# V2.net
KiCad netlist of a schematic drawn in EAGLE
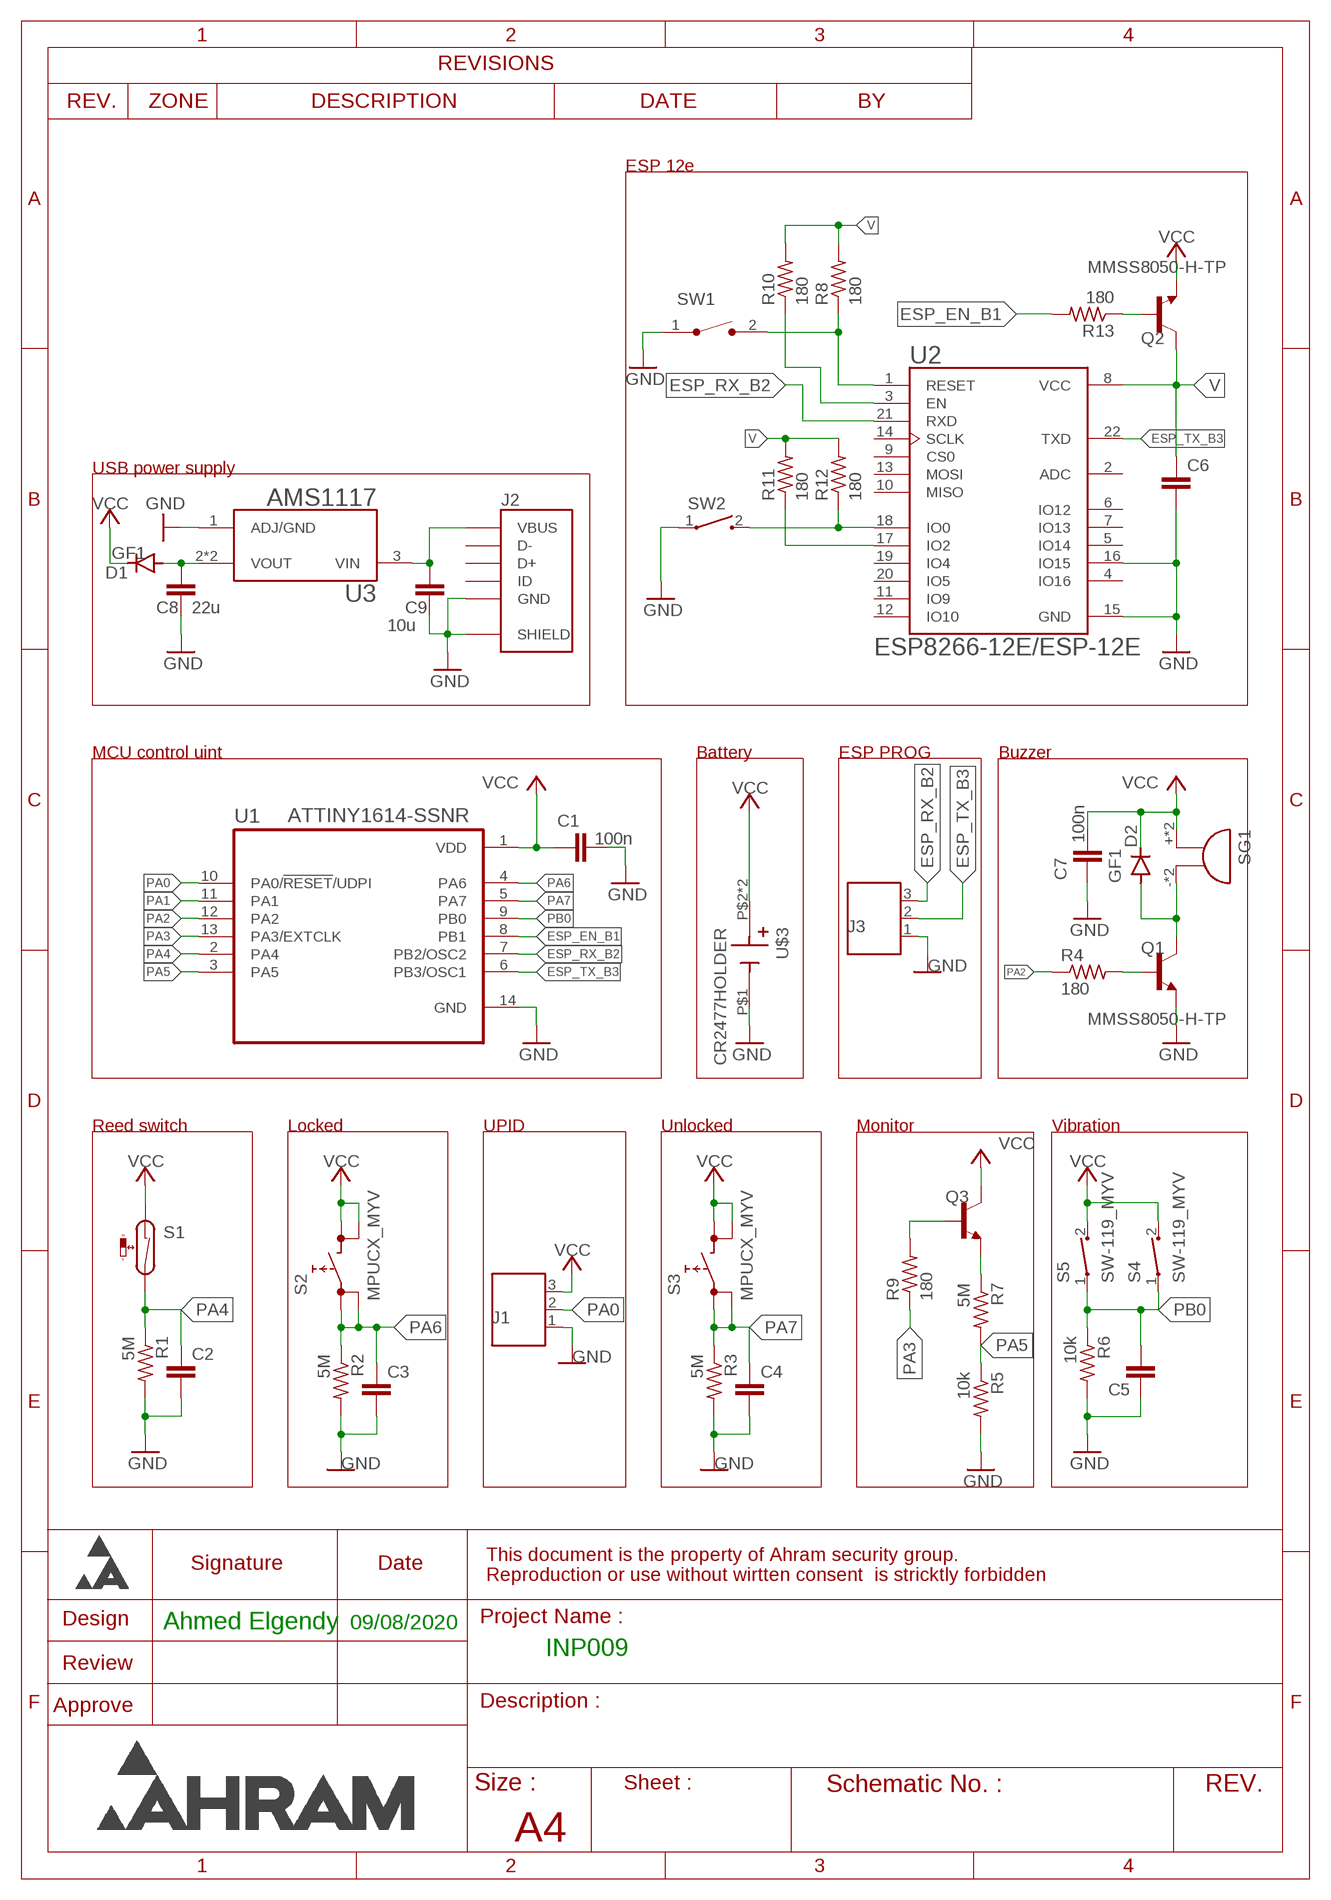
[diagram p0: schematic, sheet 1]

(export (version "E")
  (design (tool "Eeschema 10.0.6"))
  (components
    (comp (ref "C1")
      (value "100n")
      (footprint "eagle-import:C0805K")
      (libsource (lib "eagle-import") (part "C-EUC0805K"))
    )
    (comp (ref "C2")
      (value "C-EUC0805K")
      (footprint "eagle-import:C0805K")
      (libsource (lib "eagle-import") (part "C-EUC0805K"))
    )
    (comp (ref "C3")
      (value "C-EUC0805K")
      (footprint "eagle-import:C0805K")
      (libsource (lib "eagle-import") (part "C-EUC0805K"))
    )
    (comp (ref "C4")
      (value "C-EUC0805K")
      (footprint "eagle-import:C0805K")
      (libsource (lib "eagle-import") (part "C-EUC0805K"))
    )
    (comp (ref "C5")
      (value "C-EUC0805K")
      (footprint "eagle-import:C0805K")
      (libsource (lib "eagle-import") (part "C-EUC0805K"))
    )
    (comp (ref "C6")
      (value "C-EUC0805K")
      (footprint "eagle-import:C0805K")
      (libsource (lib "eagle-import") (part "C-EUC0805K"))
    )
    (comp (ref "C7")
      (value "100n")
      (footprint "eagle-import:C0805K")
      (libsource (lib "eagle-import") (part "C-EUC0805K"))
    )
    (comp (ref "C8")
      (value "22u")
      (footprint "eagle-import:C0805K")
      (libsource (lib "eagle-import") (part "C-EUC0805K"))
    )
    (comp (ref "C9")
      (value "10u")
      (footprint "eagle-import:C0805K")
      (libsource (lib "eagle-import") (part "C-EUC0805K"))
    )
    (comp (ref "D1")
      (value "GF1")
      (footprint "eagle-import:SMA-DO214AC")
      (libsource (lib "eagle-import") (part "GF1"))
    )
    (comp (ref "D2")
      (value "GF1")
      (footprint "eagle-import:SMA-DO214AC")
      (libsource (lib "eagle-import") (part "GF1"))
    )
    (comp (ref "J1")
      (value "691508110303")
      (footprint "eagle-import:691508110303")
      (libsource (lib "eagle-import") (part "691508110303"))
    )
    (comp (ref "J2")
      (value "USB3065-XX-00-A_REVE")
      (footprint "eagle-import:GCT_USB3065-XX-00-A_REVE")
      (fields (field (name "MF") "Global Connector Technology") (field (name "MP") "USB3065-30-00-A"))
      (libsource (lib "eagle-import") (part "USB3065-XX-00-A_REVE"))
    )
    (comp (ref "J3")
      (value "691508110303")
      (footprint "eagle-import:691508110303")
      (libsource (lib "eagle-import") (part "691508110303"))
    )
    (comp (ref "Q1")
      (value "MMSS8050-H-TP")
      (footprint "eagle-import:TRANS_MMSS8050-H-TP")
      (fields (field (name "MF") "Micro Commercial"))
      (libsource (lib "eagle-import") (part "MMSS8050-H-TP"))
    )
    (comp (ref "Q2")
      (value "MMSS8050-H-TP")
      (footprint "eagle-import:TRANS_MMSS8050-H-TP")
      (fields (field (name "MF") "Micro Commercial"))
      (libsource (lib "eagle-import") (part "MMSS8050-H-TP"))
    )
    (comp (ref "Q3")
      (value "MMSS8050-H-TP")
      (footprint "eagle-import:TRANS_MMSS8050-H-TP")
      (fields (field (name "MF") "Micro Commercial"))
      (libsource (lib "eagle-import") (part "MMSS8050-H-TP"))
    )
    (comp (ref "R1")
      (value "5M")
      (footprint "eagle-import:M0805")
      (libsource (lib "eagle-import") (part "R-US_M0805"))
    )
    (comp (ref "R2")
      (value "5M")
      (footprint "eagle-import:M0805")
      (libsource (lib "eagle-import") (part "R-US_M0805"))
    )
    (comp (ref "R3")
      (value "5M")
      (footprint "eagle-import:M0805")
      (libsource (lib "eagle-import") (part "R-US_M0805"))
    )
    (comp (ref "R4")
      (value "180")
      (footprint "eagle-import:M0805")
      (libsource (lib "eagle-import") (part "R-US_M0805"))
    )
    (comp (ref "R5")
      (value "10k")
      (footprint "eagle-import:M0805")
      (libsource (lib "eagle-import") (part "R-US_M0805"))
    )
    (comp (ref "R6")
      (value "10k")
      (footprint "eagle-import:M0805")
      (libsource (lib "eagle-import") (part "R-US_M0805"))
    )
    (comp (ref "R7")
      (value "5M")
      (footprint "eagle-import:M0805")
      (libsource (lib "eagle-import") (part "R-US_M0805"))
    )
    (comp (ref "R8")
      (value "180")
      (footprint "eagle-import:M0805")
      (libsource (lib "eagle-import") (part "R-US_M0805"))
    )
    (comp (ref "R9")
      (value "180")
      (footprint "eagle-import:M0805")
      (libsource (lib "eagle-import") (part "R-US_M0805"))
    )
    (comp (ref "R10")
      (value "180")
      (footprint "eagle-import:M0805")
      (libsource (lib "eagle-import") (part "R-US_M0805"))
    )
    (comp (ref "R11")
      (value "180")
      (footprint "eagle-import:M0805")
      (libsource (lib "eagle-import") (part "R-US_M0805"))
    )
    (comp (ref "R12")
      (value "180")
      (footprint "eagle-import:M0805")
      (libsource (lib "eagle-import") (part "R-US_M0805"))
    )
    (comp (ref "R13")
      (value "180")
      (footprint "eagle-import:M0805")
      (libsource (lib "eagle-import") (part "R-US_M0805"))
    )
    (comp (ref "S1")
      (value "RI80SMDM-MYV")
      (footprint "eagle-import:RI80SMDM-0510-J1")
      (libsource (lib "eagle-import") (part "RI80SMDM-MYV"))
    )
    (comp (ref "S2")
      (value "MPUCX_MYV")
      (footprint "eagle-import:MPUCX_MYV")
      (libsource (lib "eagle-import") (part "MPUCX_MYV"))
    )
    (comp (ref "S3")
      (value "MPUCX_MYV")
      (footprint "eagle-import:MPUCX_MYV")
      (libsource (lib "eagle-import") (part "MPUCX_MYV"))
    )
    (comp (ref "S4")
      (value "SW-119_MYV")
      (footprint "eagle-import:SW-119")
      (libsource (lib "eagle-import") (part "SW-119_MYV"))
    )
    (comp (ref "S5")
      (value "SW-119_MYV")
      (footprint "eagle-import:SW-119")
      (libsource (lib "eagle-import") (part "SW-119_MYV"))
    )
    (comp (ref "SG1")
      (value "CMI-9653S-SMT")
      (footprint "eagle-import:SMD_BUZZER")
      (libsource (lib "eagle-import") (part "CMI-9653S-SMT"))
    )
    (comp (ref "SW1")
      (value "FSMSM")
      (footprint "eagle-import:TE_FSMSM")
      (fields (field (name "COMMENT") "1437566-3") (field (name "MF") "TE Connectivity"))
      (libsource (lib "eagle-import") (part "FSMSM"))
    )
    (comp (ref "SW2")
      (value "1437566-3")
      (footprint "eagle-import:SW_1437566-3")
      (fields (field (name "MF") "TE Connectivity"))
      (libsource (lib "eagle-import") (part "1437566-3"))
    )
    (comp (ref "U$3")
      (value "CR2477HOLDER")
      (footprint "eagle-import:CR2477")
      (libsource (lib "eagle-import") (part "CR2477HOLDER"))
    )
    (comp (ref "U1")
      (value "ATTINY1614-SSNR")
      (footprint "eagle-import:SOIC127P600X175-14N")
      (fields (field (name "MF") "Microchip Technology"))
      (libsource (lib "eagle-import") (part "ATTINY1614-SSNR"))
    )
    (comp (ref "U2")
      (value "ESP8266-12E/ESP-12E")
      (footprint "eagle-import:XCVR_ESP8266-12E_ESP-12E")
      (fields (field (name "MF") "AI-Thinker"))
      (libsource (lib "eagle-import") (part "ESP8266-12E/ESP-12E"))
    )
    (comp (ref "U3")
      (value "AMS1117")
      (footprint "eagle-import:SOT229P700X180-4N")
      (fields (field (name "MF") "Seeed Technology"))
      (libsource (lib "eagle-import") (part "AMS1117"))
    )
  )
  (nets
    (net (code "1") (name "ESP_EN_B1") (class "Default")
      (node (ref "R13") (pin "2") (pinfunction "2_2") (pintype "passive"))
      (node (ref "U1") (pin "8") (pinfunction "PB1_8") (pintype "bidirectional"))
    )
    (net (code "2") (name "ESP_RX_B2") (class "Default")
      (node (ref "J3") (pin "3") (pinfunction "3_3") (pintype "passive"))
      (node (ref "U1") (pin "7") (pinfunction "PB2/OSC2_7") (pintype "bidirectional"))
      (node (ref "U2") (pin "21") (pinfunction "RXD_21") (pintype "input"))
    )
    (net (code "3") (name "ESP_TX_B3") (class "Default")
      (node (ref "J3") (pin "2") (pinfunction "2_2") (pintype "passive"))
      (node (ref "U1") (pin "6") (pinfunction "PB3/OSC1_6") (pintype "bidirectional"))
      (node (ref "U2") (pin "22") (pinfunction "TXD_22") (pintype "output"))
    )
    (net (code "4") (name "GND") (class "Default")
      (node (ref "C1") (pin "2") (pinfunction "2_2") (pintype "passive"))
      (node (ref "C2") (pin "2") (pinfunction "2_2") (pintype "passive"))
      (node (ref "C3") (pin "2") (pinfunction "2_2") (pintype "passive"))
      (node (ref "C4") (pin "2") (pinfunction "2_2") (pintype "passive"))
      (node (ref "C5") (pin "1") (pinfunction "1_1") (pintype "passive"))
      (node (ref "C6") (pin "2") (pinfunction "2_2") (pintype "passive"))
      (node (ref "C7") (pin "1") (pinfunction "1_1") (pintype "passive"))
      (node (ref "C8") (pin "1") (pinfunction "1_1") (pintype "passive"))
      (node (ref "C9") (pin "1") (pinfunction "1_1") (pintype "passive"))
      (node (ref "J1") (pin "1") (pinfunction "1_1") (pintype "passive"))
      (node (ref "J2") (pin "5") (pinfunction "GND_5") (pintype "power_in"))
      (node (ref "J2") (pin "6") (pinfunction "SHIELD_6") (pintype "power_in"))
      (node (ref "J2") (pin "7") (pinfunction "SHIELD_7") (pintype "power_in"))
      (node (ref "J2") (pin "8") (pinfunction "SHIELD_8") (pintype "power_in"))
      (node (ref "J2") (pin "9") (pinfunction "SHIELD_9") (pintype "power_in"))
      (node (ref "J3") (pin "1") (pinfunction "1_1") (pintype "passive"))
      (node (ref "Q1") (pin "2") (pinfunction "E_2") (pintype "passive"))
      (node (ref "R1") (pin "2") (pinfunction "2_2") (pintype "passive"))
      (node (ref "R2") (pin "2") (pinfunction "2_2") (pintype "passive"))
      (node (ref "R3") (pin "2") (pinfunction "2_2") (pintype "passive"))
      (node (ref "R5") (pin "2") (pinfunction "2_2") (pintype "passive"))
      (node (ref "R6") (pin "2") (pinfunction "2_2") (pintype "passive"))
      (node (ref "SW1") (pin "1") (pinfunction "1_1") (pintype "passive"))
      (node (ref "SW2") (pin "1") (pinfunction "1_1") (pintype "passive"))
      (node (ref "U$3") (pin "P$1") (pinfunction "-_P$1") (pintype "passive"))
      (node (ref "U1") (pin "14") (pinfunction "GND_14") (pintype "power_in"))
      (node (ref "U2") (pin "15") (pinfunction "GND_15") (pintype "power_in"))
      (node (ref "U2") (pin "16") (pinfunction "IO15_16") (pintype "bidirectional"))
      (node (ref "U3") (pin "1") (pinfunction "ADJ/GND_1") (pintype "power_in"))
    )
    (net (code "5") (name "Net-(C8-Pad2)") (class "Default")
      (node (ref "C8") (pin "2") (pinfunction "2_2") (pintype "passive"))
      (node (ref "D1") (pin "A") (pinfunction "A_A") (pintype "passive"))
      (node (ref "U3") (pin "2") (pinfunction "VOUT_2") (pintype "output"))
      (node (ref "U3") (pin "4") (pinfunction "VOUT_4") (pintype "output"))
    )
    (net (code "6") (name "Net-(J2-VBUS)") (class "Default")
      (node (ref "C9") (pin "2") (pinfunction "2_2") (pintype "passive"))
      (node (ref "J2") (pin "1") (pinfunction "VBUS_1") (pintype "power_in"))
      (node (ref "U3") (pin "3") (pinfunction "VIN_3") (pintype "input"))
    )
    (net (code "7") (name "Net-(Q1-B)") (class "Default")
      (node (ref "Q1") (pin "1") (pinfunction "B_1") (pintype "passive"))
      (node (ref "R4") (pin "2") (pinfunction "2_2") (pintype "passive"))
    )
    (net (code "8") (name "Net-(Q1-C)") (class "Default")
      (node (ref "D2") (pin "A") (pinfunction "A_A") (pintype "passive"))
      (node (ref "Q1") (pin "3") (pinfunction "C_3") (pintype "passive"))
      (node (ref "SG1") (pin "-") (pinfunction "-_-") (pintype "passive"))
      (node (ref "SG1") (pin "--") (pinfunction "-_--") (pintype "passive"))
    )
    (net (code "9") (name "Net-(Q2-B)") (class "Default")
      (node (ref "Q2") (pin "1") (pinfunction "B_1") (pintype "passive"))
      (node (ref "R13") (pin "1") (pinfunction "1_1") (pintype "passive"))
    )
    (net (code "10") (name "Net-(Q3-B)") (class "Default")
      (node (ref "Q3") (pin "1") (pinfunction "B_1") (pintype "passive"))
      (node (ref "R9") (pin "2") (pinfunction "2_2") (pintype "passive"))
    )
    (net (code "11") (name "Net-(Q3-E)") (class "Default")
      (node (ref "Q3") (pin "2") (pinfunction "E_2") (pintype "passive"))
      (node (ref "R7") (pin "1") (pinfunction "1_1") (pintype "passive"))
    )
    (net (code "12") (name "Net-(U2-EN)") (class "Default")
      (node (ref "R10") (pin "1") (pinfunction "1_1") (pintype "passive"))
      (node (ref "U2") (pin "3") (pinfunction "EN_3") (pintype "input"))
    )
    (net (code "13") (name "Net-(U2-IO0)") (class "Default")
      (node (ref "R12") (pin "1") (pinfunction "1_1") (pintype "passive"))
      (node (ref "SW2") (pin "2") (pinfunction "2_2") (pintype "passive"))
      (node (ref "U2") (pin "18") (pinfunction "IO0_18") (pintype "bidirectional"))
    )
    (net (code "14") (name "Net-(U2-IO2)") (class "Default")
      (node (ref "R11") (pin "1") (pinfunction "1_1") (pintype "passive"))
      (node (ref "U2") (pin "17") (pinfunction "IO2_17") (pintype "bidirectional"))
    )
    (net (code "15") (name "Net-(U2-RESET)") (class "Default")
      (node (ref "R8") (pin "1") (pinfunction "1_1") (pintype "passive"))
      (node (ref "SW1") (pin "2") (pinfunction "2_2") (pintype "passive"))
      (node (ref "U2") (pin "1") (pinfunction "RESET_1") (pintype "input"))
    )
    (net (code "16") (name "PA0") (class "Default")
      (node (ref "J1") (pin "2") (pinfunction "2_2") (pintype "passive"))
      (node (ref "U1") (pin "10") (pinfunction "PA0/~{RESET}/UDPI_10") (pintype "bidirectional"))
    )
    (net (code "17") (name "PA1") (class "Default")
      (node (ref "U1") (pin "11") (pinfunction "PA1_11") (pintype "bidirectional"))
    )
    (net (code "18") (name "PA2") (class "Default")
      (node (ref "R4") (pin "1") (pinfunction "1_1") (pintype "passive"))
      (node (ref "U1") (pin "12") (pinfunction "PA2_12") (pintype "bidirectional"))
    )
    (net (code "19") (name "PA3") (class "Default")
      (node (ref "R9") (pin "1") (pinfunction "1_1") (pintype "passive"))
      (node (ref "U1") (pin "13") (pinfunction "PA3/EXTCLK_13") (pintype "bidirectional"))
    )
    (net (code "20") (name "PA4") (class "Default")
      (node (ref "C2") (pin "1") (pinfunction "1_1") (pintype "passive"))
      (node (ref "R1") (pin "1") (pinfunction "1_1") (pintype "passive"))
      (node (ref "S1") (pin "P$2") (pinfunction "2_P$2") (pintype "passive"))
      (node (ref "U1") (pin "2") (pinfunction "PA4_2") (pintype "bidirectional"))
    )
    (net (code "21") (name "PA5") (class "Default")
      (node (ref "R5") (pin "1") (pinfunction "1_1") (pintype "passive"))
      (node (ref "R7") (pin "2") (pinfunction "2_2") (pintype "passive"))
      (node (ref "U1") (pin "3") (pinfunction "PA5_3") (pintype "bidirectional"))
    )
    (net (code "22") (name "PA6") (class "Default")
      (node (ref "C3") (pin "1") (pinfunction "1_1") (pintype "passive"))
      (node (ref "R2") (pin "1") (pinfunction "1_1") (pintype "passive"))
      (node (ref "S2") (pin "1") (pinfunction "1_1") (pintype "passive"))
      (node (ref "S2") (pin "2") (pinfunction "2_2") (pintype "passive"))
      (node (ref "U1") (pin "4") (pinfunction "PA6_4") (pintype "bidirectional"))
    )
    (net (code "23") (name "PA7") (class "Default")
      (node (ref "C4") (pin "1") (pinfunction "1_1") (pintype "passive"))
      (node (ref "R3") (pin "1") (pinfunction "1_1") (pintype "passive"))
      (node (ref "S3") (pin "1") (pinfunction "1_1") (pintype "passive"))
      (node (ref "S3") (pin "2") (pinfunction "2_2") (pintype "passive"))
      (node (ref "U1") (pin "5") (pinfunction "PA7_5") (pintype "bidirectional"))
    )
    (net (code "24") (name "PB0") (class "Default")
      (node (ref "C5") (pin "2") (pinfunction "2_2") (pintype "passive"))
      (node (ref "R6") (pin "1") (pinfunction "1_1") (pintype "passive"))
      (node (ref "S4") (pin "1") (pinfunction "1_1") (pintype "passive"))
      (node (ref "S5") (pin "1") (pinfunction "1_1") (pintype "passive"))
      (node (ref "U1") (pin "9") (pinfunction "PB0_9") (pintype "bidirectional"))
    )
    (net (code "25") (name "V") (class "Default")
      (node (ref "C6") (pin "1") (pinfunction "1_1") (pintype "passive"))
      (node (ref "Q2") (pin "3") (pinfunction "C_3") (pintype "passive"))
      (node (ref "R10") (pin "2") (pinfunction "2_2") (pintype "passive"))
      (node (ref "R11") (pin "2") (pinfunction "2_2") (pintype "passive"))
      (node (ref "R12") (pin "2") (pinfunction "2_2") (pintype "passive"))
      (node (ref "R8") (pin "2") (pinfunction "2_2") (pintype "passive"))
      (node (ref "U2") (pin "8") (pinfunction "VCC_8") (pintype "power_in"))
    )
    (net (code "26") (name "VCC") (class "Default")
      (node (ref "C1") (pin "1") (pinfunction "1_1") (pintype "passive"))
      (node (ref "C7") (pin "2") (pinfunction "2_2") (pintype "passive"))
      (node (ref "D1") (pin "K") (pinfunction "C_K") (pintype "passive"))
      (node (ref "D2") (pin "K") (pinfunction "C_K") (pintype "passive"))
      (node (ref "J1") (pin "3") (pinfunction "3_3") (pintype "passive"))
      (node (ref "Q2") (pin "2") (pinfunction "E_2") (pintype "passive"))
      (node (ref "Q3") (pin "3") (pinfunction "C_3") (pintype "passive"))
      (node (ref "S1") (pin "P$1") (pinfunction "1_P$1") (pintype "passive"))
      (node (ref "S2") (pin "3") (pinfunction "3_3") (pintype "passive"))
      (node (ref "S2") (pin "4") (pinfunction "4_4") (pintype "passive"))
      (node (ref "S3") (pin "3") (pinfunction "3_3") (pintype "passive"))
      (node (ref "S3") (pin "4") (pinfunction "4_4") (pintype "passive"))
      (node (ref "S4") (pin "2") (pinfunction "2_2") (pintype "passive"))
      (node (ref "S5") (pin "2") (pinfunction "2_2") (pintype "passive"))
      (node (ref "SG1") (pin "+") (pinfunction "+_+") (pintype "passive"))
      (node (ref "SG1") (pin "++") (pinfunction "+_++") (pintype "passive"))
      (node (ref "U$3") (pin "P$2") (pinfunction "+_P$2") (pintype "passive"))
      (node (ref "U$3") (pin "P$3") (pinfunction "+_P$3") (pintype "passive"))
      (node (ref "U1") (pin "1") (pinfunction "VDD_1") (pintype "power_in"))
    )
    (net (code "27") (name "unconnected-(J2-D+-Pad3)") (class "Default")
      (node (ref "J2") (pin "3") (pinfunction "D+_3") (pintype "bidirectional"))
    )
    (net (code "28") (name "unconnected-(J2-D--Pad2)") (class "Default")
      (node (ref "J2") (pin "2") (pinfunction "D-_2") (pintype "bidirectional"))
    )
    (net (code "29") (name "unconnected-(J2-ID-Pad4)") (class "Default")
      (node (ref "J2") (pin "4") (pinfunction "ID_4") (pintype "bidirectional"))
    )
    (net (code "30") (name "unconnected-(U2-ADC-Pad2)") (class "Default")
      (node (ref "U2") (pin "2") (pinfunction "ADC_2") (pintype "passive"))
    )
    (net (code "31") (name "unconnected-(U2-CS0-Pad9)") (class "Default")
      (node (ref "U2") (pin "9") (pinfunction "CS0_9") (pintype "input"))
    )
    (net (code "32") (name "unconnected-(U2-IO4-Pad19)") (class "Default")
      (node (ref "U2") (pin "19") (pinfunction "IO4_19") (pintype "bidirectional"))
    )
    (net (code "33") (name "unconnected-(U2-IO5-Pad20)") (class "Default")
      (node (ref "U2") (pin "20") (pinfunction "IO5_20") (pintype "bidirectional"))
    )
    (net (code "34") (name "unconnected-(U2-IO9-Pad11)") (class "Default")
      (node (ref "U2") (pin "11") (pinfunction "IO9_11") (pintype "bidirectional"))
    )
    (net (code "35") (name "unconnected-(U2-IO10-Pad12)") (class "Default")
      (node (ref "U2") (pin "12") (pinfunction "IO10_12") (pintype "bidirectional"))
    )
    (net (code "36") (name "unconnected-(U2-IO12-Pad6)") (class "Default")
      (node (ref "U2") (pin "6") (pinfunction "IO12_6") (pintype "bidirectional"))
    )
    (net (code "37") (name "unconnected-(U2-IO13-Pad7)") (class "Default")
      (node (ref "U2") (pin "7") (pinfunction "IO13_7") (pintype "bidirectional"))
    )
    (net (code "38") (name "unconnected-(U2-IO14-Pad5)") (class "Default")
      (node (ref "U2") (pin "5") (pinfunction "IO14_5") (pintype "bidirectional"))
    )
    (net (code "39") (name "unconnected-(U2-IO16-Pad4)") (class "Default")
      (node (ref "U2") (pin "4") (pinfunction "IO16_4") (pintype "bidirectional"))
    )
    (net (code "40") (name "unconnected-(U2-MISO-Pad10)") (class "Default")
      (node (ref "U2") (pin "10") (pinfunction "MISO_10") (pintype "bidirectional"))
    )
    (net (code "41") (name "unconnected-(U2-MOSI-Pad13)") (class "Default")
      (node (ref "U2") (pin "13") (pinfunction "MOSI_13") (pintype "bidirectional"))
    )
    (net (code "42") (name "unconnected-(U2-SCLK-Pad14)") (class "Default")
      (node (ref "U2") (pin "14") (pinfunction "SCLK_14") (pintype "input"))
    )
  )
)
